# interface.net
KiCad netlist of a schematic drawn in Altium Designer
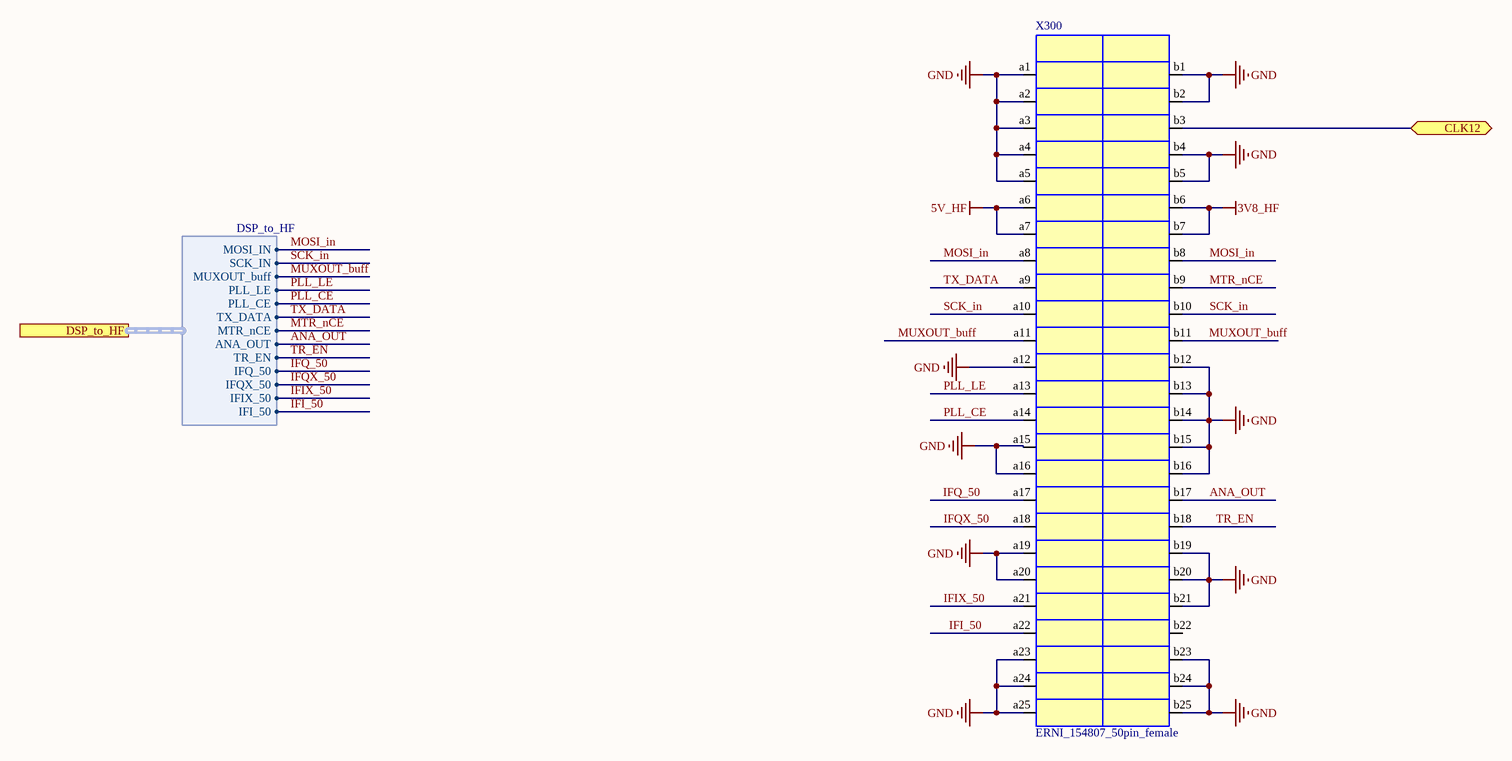
[diagram p0: interface.SchDoc]

(export (version "E")
  (design (tool "Eeschema 10.0.6"))
  (components
    (comp (ref "X300")
      (value "ERNI_154807_50pin_female")
      (footprint "ERNI_SMC_50_PINM")
      (libsource (lib "zynq_board") (part "ERNI_154807_50pin_female"))
    )
  )
  (nets
    (net (code "2") (name "/ANA_OUT") (class "Default") (node (ref "X300") (pin "b17") (pintype "passive")))
    (net (code "3") (name "/CLK12") (class "Default") (node (ref "X300") (pin "b3") (pintype "passive")))
    (net (code "4") (name "/IFIX_50") (class "Default") (node (ref "X300") (pin "a21") (pintype "passive")))
    (net (code "5") (name "/IFI_50") (class "Default") (node (ref "X300") (pin "a22") (pintype "passive")))
    (net (code "6") (name "/IFQX_50") (class "Default") (node (ref "X300") (pin "a18") (pintype "passive")))
    (net (code "7") (name "/IFQ_50") (class "Default") (node (ref "X300") (pin "a17") (pintype "passive")))
    (net (code "8") (name "/MOSI_in") (class "Default")
      (node (ref "X300") (pin "a8") (pintype "passive"))
      (node (ref "X300") (pin "b8") (pintype "passive"))
    )
    (net (code "9") (name "/MTR_nCE") (class "Default") (node (ref "X300") (pin "b9") (pintype "passive")))
    (net (code "10") (name "/MUXOUT_buff") (class "Default")
      (node (ref "X300") (pin "a11") (pintype "passive"))
      (node (ref "X300") (pin "b11") (pintype "passive"))
    )
    (net (code "11") (name "/PLL_CE") (class "Default") (node (ref "X300") (pin "a14") (pintype "passive")))
    (net (code "12") (name "/PLL_LE") (class "Default") (node (ref "X300") (pin "a13") (pintype "passive")))
    (net (code "13") (name "/SCK_in") (class "Default")
      (node (ref "X300") (pin "a10") (pintype "passive"))
      (node (ref "X300") (pin "b10") (pintype "passive"))
    )
    (net (code "14") (name "/TR_EN") (class "Default") (node (ref "X300") (pin "b18") (pintype "passive")))
    (net (code "15") (name "/TX_DATA") (class "Default") (node (ref "X300") (pin "a9") (pintype "passive")))
    (net (code "17") (name "3V8_HF") (class "Default")
      (node (ref "X300") (pin "b6") (pintype "passive"))
      (node (ref "X300") (pin "b7") (pintype "passive"))
    )
    (net (code "18") (name "5V_HF") (class "Default")
      (node (ref "X300") (pin "a6") (pintype "passive"))
      (node (ref "X300") (pin "a7") (pintype "passive"))
    )
    (net (code "19") (name "GND") (class "Default")
      (node (ref "X300") (pin "a1") (pintype "passive"))
      (node (ref "X300") (pin "a12") (pintype "passive"))
      (node (ref "X300") (pin "a15") (pintype "passive"))
      (node (ref "X300") (pin "a16") (pintype "passive"))
      (node (ref "X300") (pin "a19") (pintype "passive"))
      (node (ref "X300") (pin "a2") (pintype "passive"))
      (node (ref "X300") (pin "a20") (pintype "passive"))
      (node (ref "X300") (pin "a23") (pintype "passive"))
      (node (ref "X300") (pin "a24") (pintype "passive"))
      (node (ref "X300") (pin "a25") (pintype "passive"))
      (node (ref "X300") (pin "a3") (pintype "passive"))
      (node (ref "X300") (pin "a4") (pintype "passive"))
      (node (ref "X300") (pin "a5") (pintype "passive"))
      (node (ref "X300") (pin "b1") (pintype "passive"))
      (node (ref "X300") (pin "b12") (pintype "passive"))
      (node (ref "X300") (pin "b13") (pintype "passive"))
      (node (ref "X300") (pin "b14") (pintype "passive"))
      (node (ref "X300") (pin "b15") (pintype "passive"))
      (node (ref "X300") (pin "b16") (pintype "passive"))
      (node (ref "X300") (pin "b19") (pintype "passive"))
      (node (ref "X300") (pin "b2") (pintype "passive"))
      (node (ref "X300") (pin "b20") (pintype "passive"))
      (node (ref "X300") (pin "b21") (pintype "passive"))
      (node (ref "X300") (pin "b23") (pintype "passive"))
      (node (ref "X300") (pin "b24") (pintype "passive"))
      (node (ref "X300") (pin "b25") (pintype "passive"))
      (node (ref "X300") (pin "b4") (pintype "passive"))
      (node (ref "X300") (pin "b5") (pintype "passive"))
    )
    (net (code "20") (name "unconnected-(X300-Padb22)") (class "Default")
      (node (ref "X300") (pin "b22") (pintype "passive"))
    )
  )
)
